# schematic.net
KiCad netlist of a schematic drawn in EasyEDA
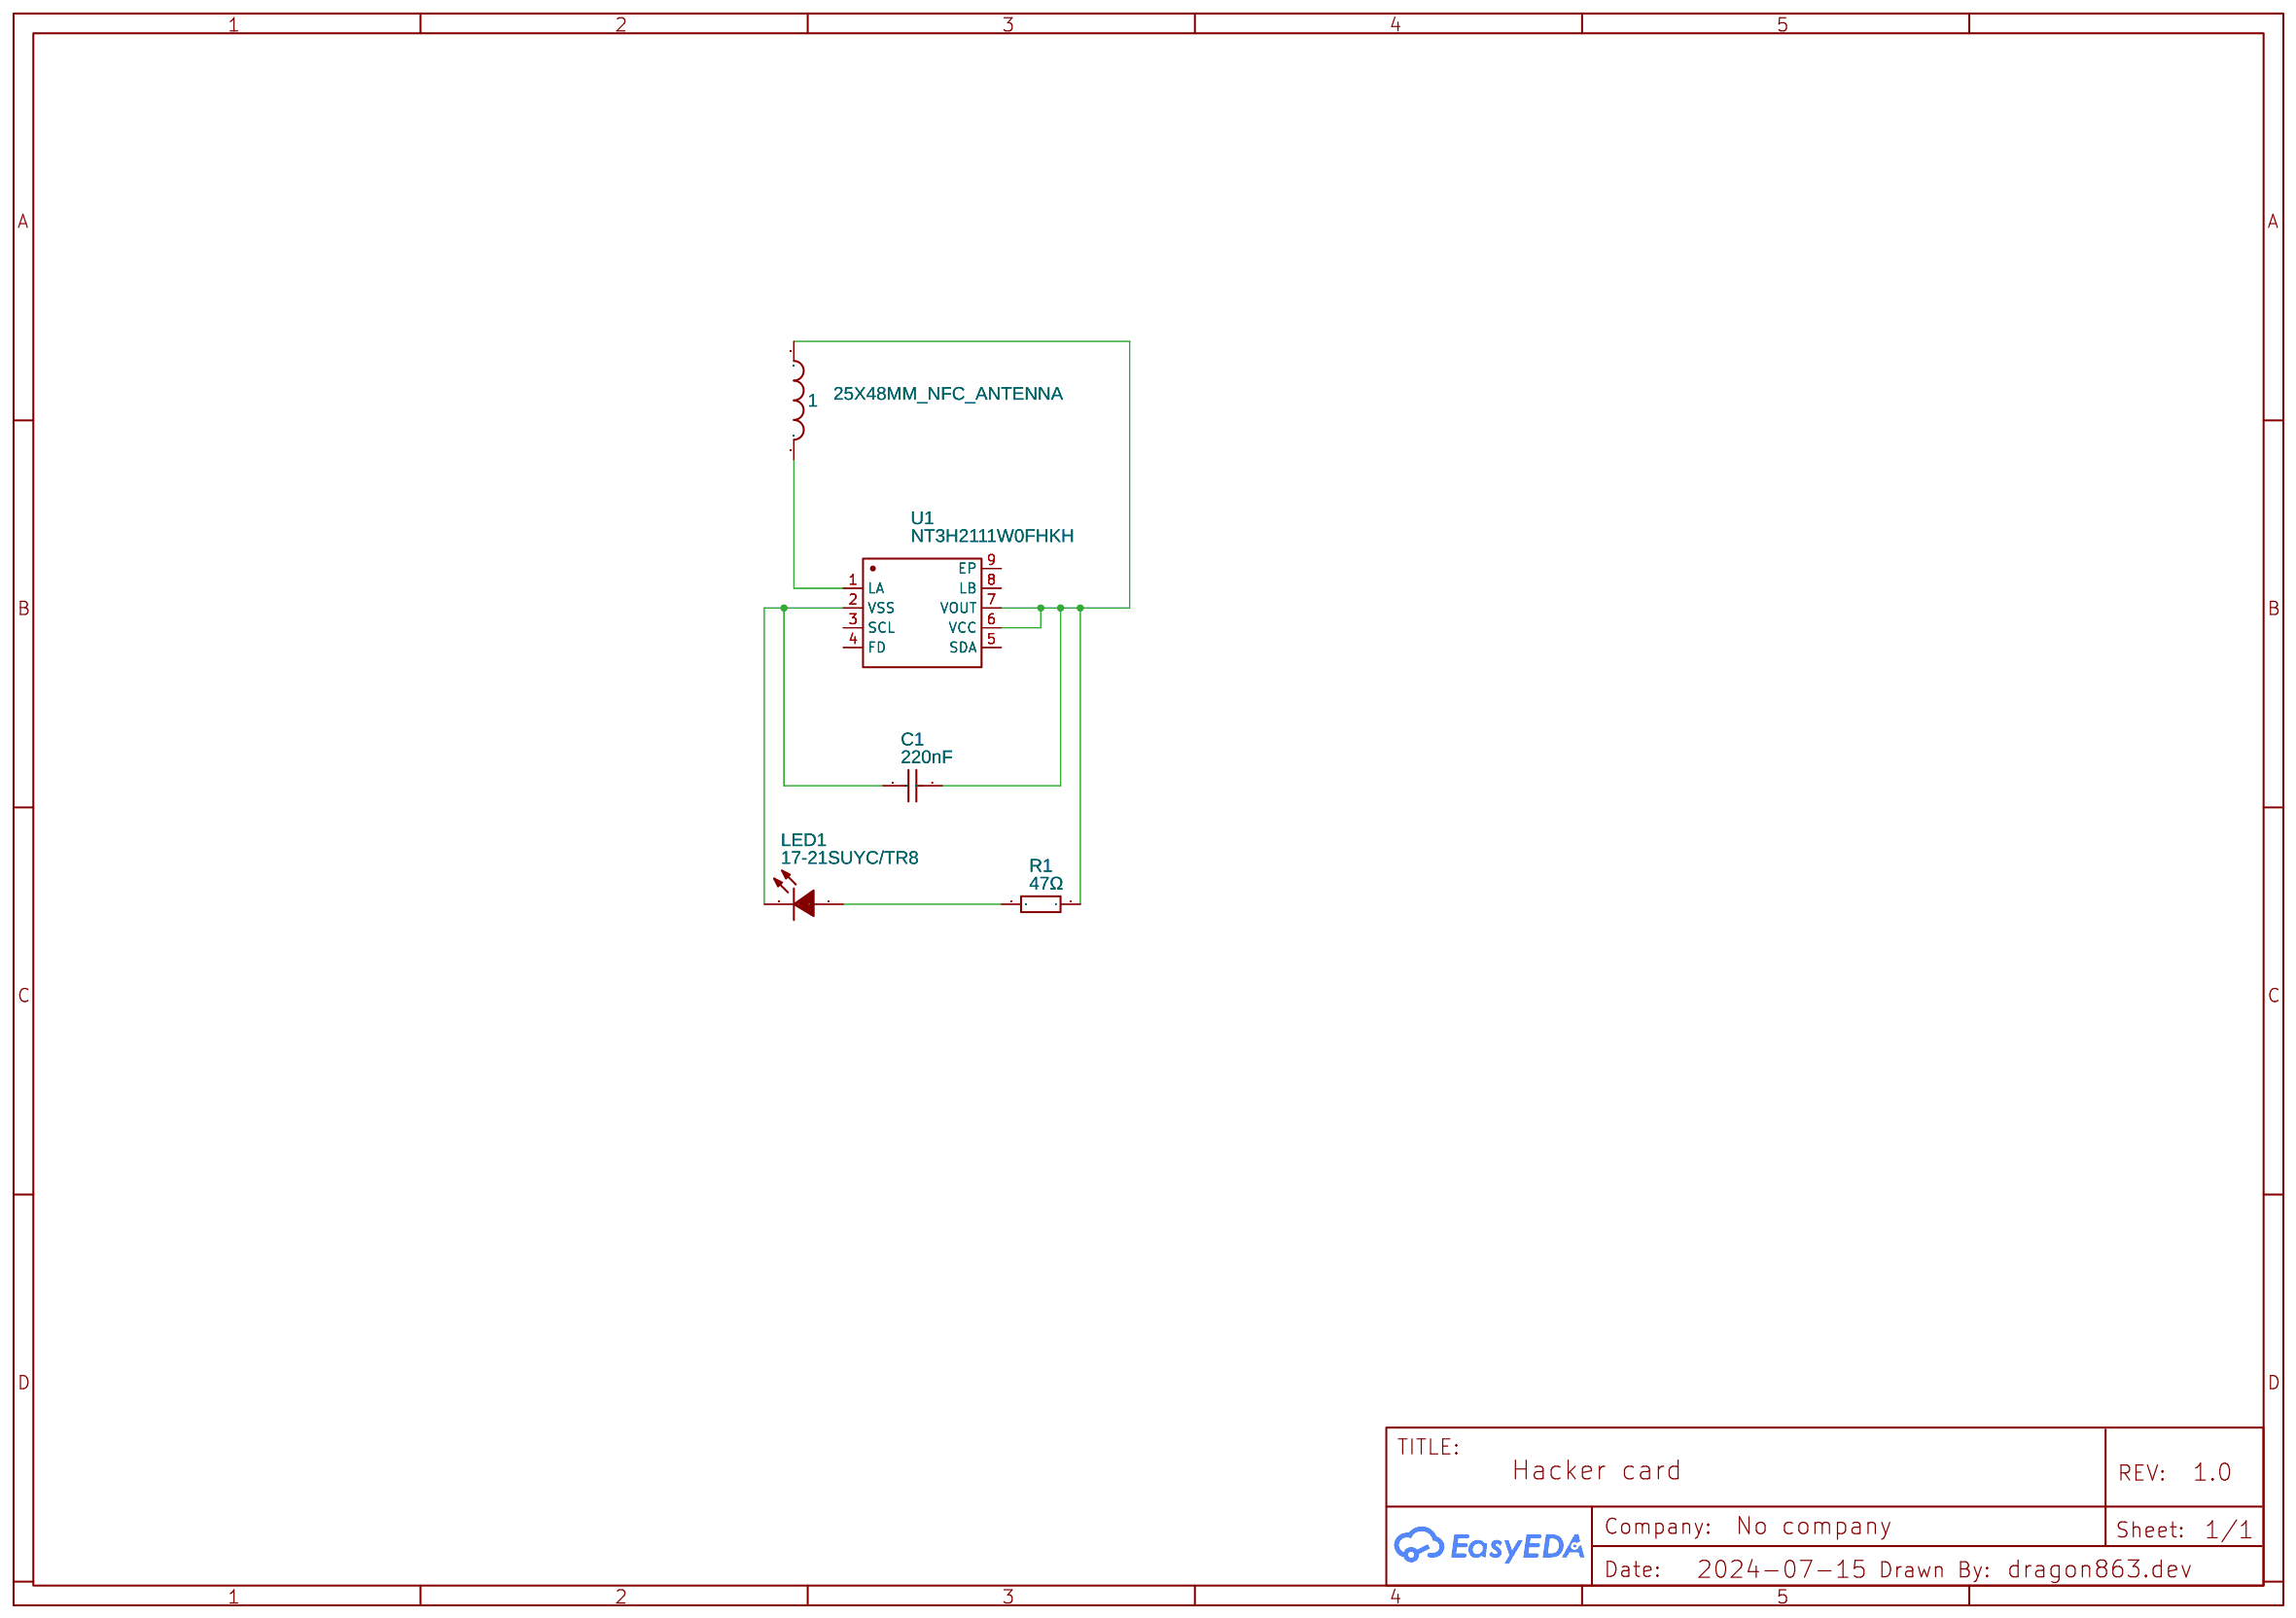
[diagram p0: schematic sheet]

(export (version "E")
  (design (tool "Eeschema 10.0.6"))
  (components
    (comp (ref "1") (value "25X48MM_NFC_ANTENNA") (libsource (lib "") (part "25X48MM_NFC_ANTENNA")))
    (comp (ref "C1")
      (value "220nF")
      (fields
        (field (name "Manufacturer Part") "CL10B224KA8NNNC")
        (field (name "Manufacturer") "SAMSUNG(三星)")
      )
      (libsource (lib "") (part "CL10B224KA8NNNC"))
    )
    (comp (ref "LED1")
      (value "17-21SUYC/TR8")
      (fields (field (name "Manufacturer Part") "KT-0805黄灯") (field (name "Manufacturer") "KENTO"))
      (libsource (lib "") (part "17-21SUYC/TR8"))
    )
    (comp (ref "R1")
      (value "47Ω")
      (fields
        (field (name "Manufacturer Part") "0603WAF470JT5E")
        (field (name "Manufacturer") "UNI-ROYAL(厚声)")
      )
      (libsource (lib "") (part "0603WAF470JT5E"))
    )
    (comp (ref "U1")
      (value "NT3H2111W0FHKH")
      (fields (field (name "Manufacturer") "NXP(恩智浦)"))
      (libsource (lib "") (part "NT3H2111W0FHKH"))
    )
  )
  (nets
    (net (code "1") (name "Net-(LED1-+)") (class "Default")
      (node (ref "LED1") (pin "1") (pinfunction "+_1") (pintype "unspecified"))
      (node (ref "R1") (pin "1") (pinfunction "1_1") (pintype "input"))
    )
    (net (code "2") (name "Net-(LED1--)") (class "Default")
      (node (ref "C1") (pin "1") (pinfunction "1_1") (pintype "input"))
      (node (ref "LED1") (pin "2") (pinfunction "-_2") (pintype "unspecified"))
      (node (ref "U1") (pin "2") (pinfunction "VSS_2") (pintype "unspecified"))
    )
    (net (code "3") (name "Net-(U1-LA)") (class "Default")
      (node (ref "1") (pin "P$2") (pinfunction "P$2_P$2") (pintype "bidirectional"))
      (node (ref "U1") (pin "1") (pinfunction "LA_1") (pintype "unspecified"))
    )
    (net (code "4") (name "Net-(U1-VCC)") (class "Default")
      (node (ref "1") (pin "P$1") (pinfunction "P$1_P$1") (pintype "bidirectional"))
      (node (ref "C1") (pin "2") (pinfunction "2_2") (pintype "input"))
      (node (ref "R1") (pin "2") (pinfunction "2_2") (pintype "input"))
      (node (ref "U1") (pin "6") (pinfunction "VCC_6") (pintype "unspecified"))
      (node (ref "U1") (pin "7") (pinfunction "VOUT_7") (pintype "unspecified"))
    )
    (net (code "5") (name "unconnected-(U1-EP-Pad9)") (class "Default")
      (node (ref "U1") (pin "9") (pinfunction "EP_9") (pintype "unspecified"))
    )
    (net (code "6") (name "unconnected-(U1-FD-Pad4)") (class "Default")
      (node (ref "U1") (pin "4") (pinfunction "FD_4") (pintype "unspecified"))
    )
    (net (code "7") (name "unconnected-(U1-LB-Pad8)") (class "Default")
      (node (ref "U1") (pin "8") (pinfunction "LB_8") (pintype "unspecified"))
    )
    (net (code "8") (name "unconnected-(U1-SCL-Pad3)") (class "Default")
      (node (ref "U1") (pin "3") (pinfunction "SCL_3") (pintype "unspecified"))
    )
    (net (code "9") (name "unconnected-(U1-SDA-Pad5)") (class "Default")
      (node (ref "U1") (pin "5") (pinfunction "SDA_5") (pintype "unspecified"))
    )
  )
)
